# RumiCarGen3-Sensor3.net
KiCad netlist of a schematic drawn in EAGLE
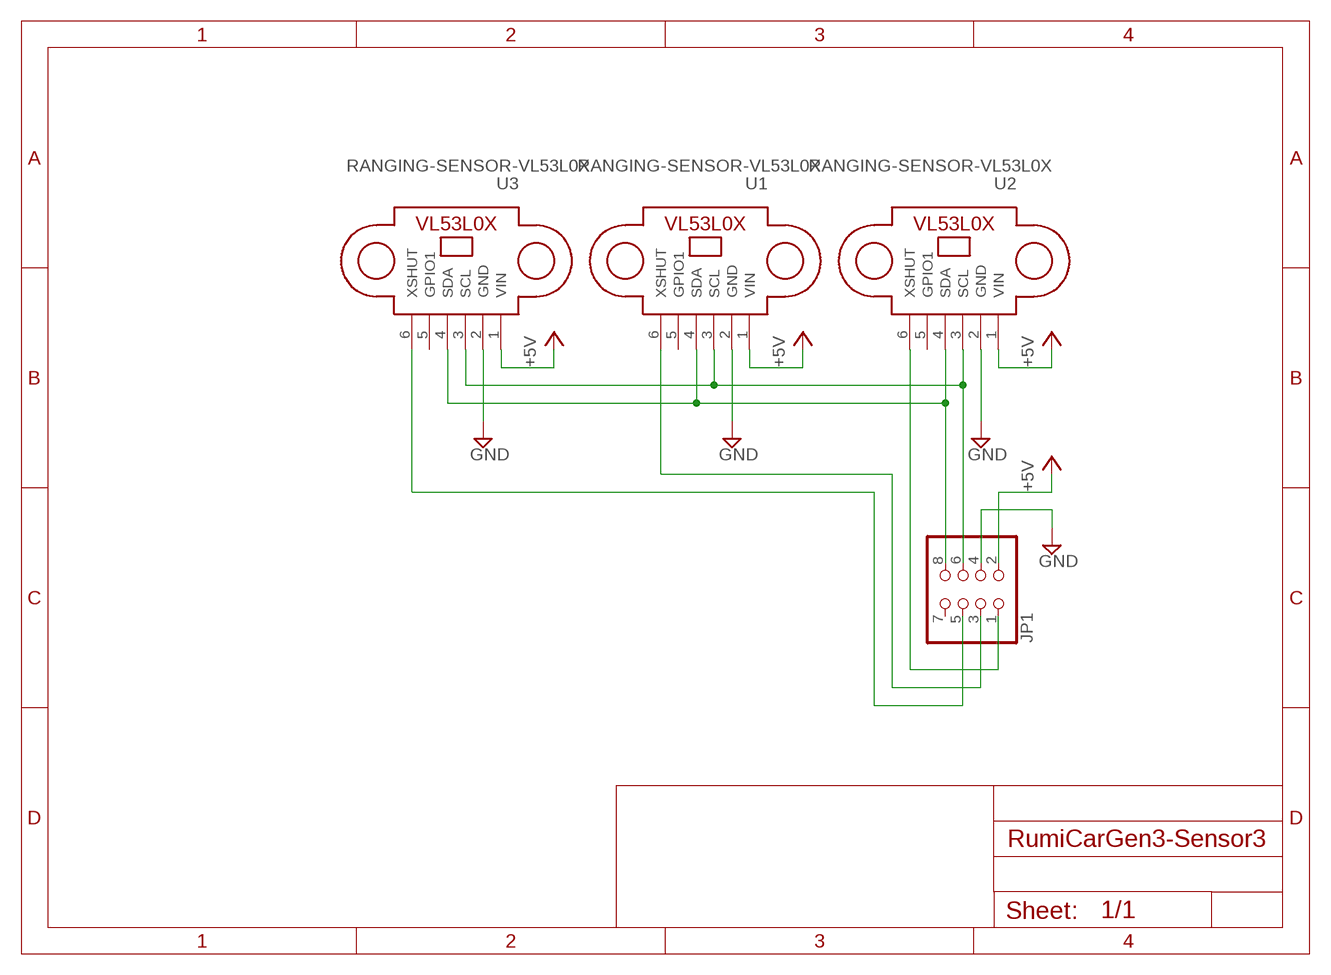
[diagram p0: schematic, sheet 1]

(export (version "E")
  (design (tool "Eeschema 10.0.6"))
  (components
    (comp (ref "JP1")
      (value "PINHD-2X4")
      (footprint "eagle-import:2X04")
      (libsource (lib "eagle-import") (part "PINHD-2X4"))
    )
    (comp (ref "U1")
      (value "RANGING-SENSOR-VL53L0X")
      (footprint "eagle-import:RANGING-SENSOR-VL53L0X")
      (libsource (lib "eagle-import") (part "RANGING-SENSOR-VL53L0X"))
    )
    (comp (ref "U2")
      (value "RANGING-SENSOR-VL53L0X")
      (footprint "eagle-import:RANGING-SENSOR-VL53L0X")
      (libsource (lib "eagle-import") (part "RANGING-SENSOR-VL53L0X"))
    )
    (comp (ref "U3")
      (value "RANGING-SENSOR-VL53L0X")
      (footprint "eagle-import:RANGING-SENSOR-VL53L0X")
      (libsource (lib "eagle-import") (part "RANGING-SENSOR-VL53L0X"))
    )
  )
  (nets
    (net (code "1") (name "+5V") (class "Default")
      (node (ref "JP1") (pin "2") (pinfunction "2_2") (pintype "passive"))
      (node (ref "U1") (pin "1") (pinfunction "VIN_1") (pintype "power_in"))
      (node (ref "U2") (pin "1") (pinfunction "VIN_1") (pintype "power_in"))
      (node (ref "U3") (pin "1") (pinfunction "VIN_1") (pintype "power_in"))
    )
    (net (code "2") (name "GND") (class "Default")
      (node (ref "JP1") (pin "4") (pinfunction "4_4") (pintype "passive"))
      (node (ref "U1") (pin "2") (pinfunction "GND_2") (pintype "power_in"))
      (node (ref "U2") (pin "2") (pinfunction "GND_2") (pintype "power_in"))
      (node (ref "U3") (pin "2") (pinfunction "GND_2") (pintype "power_in"))
    )
    (net (code "3") (name "Net-(U1-SCL)") (class "Default")
      (node (ref "JP1") (pin "6") (pinfunction "6_6") (pintype "passive"))
      (node (ref "U1") (pin "3") (pinfunction "SCL_3") (pintype "bidirectional"))
      (node (ref "U2") (pin "3") (pinfunction "SCL_3") (pintype "bidirectional"))
      (node (ref "U3") (pin "3") (pinfunction "SCL_3") (pintype "bidirectional"))
    )
    (net (code "4") (name "Net-(U1-SDA)") (class "Default")
      (node (ref "JP1") (pin "8") (pinfunction "8_8") (pintype "passive"))
      (node (ref "U1") (pin "4") (pinfunction "SDA_4") (pintype "bidirectional"))
      (node (ref "U2") (pin "4") (pinfunction "SDA_4") (pintype "bidirectional"))
      (node (ref "U3") (pin "4") (pinfunction "SDA_4") (pintype "bidirectional"))
    )
    (net (code "5") (name "Net-(U1-XSHUT)") (class "Default")
      (node (ref "JP1") (pin "3") (pinfunction "3_3") (pintype "passive"))
      (node (ref "U1") (pin "6") (pinfunction "XSHUT_6") (pintype "bidirectional"))
    )
    (net (code "6") (name "Net-(U2-XSHUT)") (class "Default")
      (node (ref "JP1") (pin "1") (pinfunction "1_1") (pintype "passive"))
      (node (ref "U2") (pin "6") (pinfunction "XSHUT_6") (pintype "bidirectional"))
    )
    (net (code "7") (name "Net-(U3-XSHUT)") (class "Default")
      (node (ref "JP1") (pin "5") (pinfunction "5_5") (pintype "passive"))
      (node (ref "U3") (pin "6") (pinfunction "XSHUT_6") (pintype "bidirectional"))
    )
    (net (code "8") (name "unconnected-(JP1-Pad7)") (class "Default")
      (node (ref "JP1") (pin "7") (pinfunction "7_7") (pintype "passive"))
    )
    (net (code "9") (name "unconnected-(U1-GPIO1-Pad5)") (class "Default")
      (node (ref "U1") (pin "5") (pinfunction "GPIO1_5") (pintype "bidirectional"))
    )
    (net (code "10") (name "unconnected-(U2-GPIO1-Pad5)") (class "Default")
      (node (ref "U2") (pin "5") (pinfunction "GPIO1_5") (pintype "bidirectional"))
    )
    (net (code "11") (name "unconnected-(U3-GPIO1-Pad5)") (class "Default")
      (node (ref "U3") (pin "5") (pinfunction "GPIO1_5") (pintype "bidirectional"))
    )
  )
)
